# SK3000v1_-_3.net
KiCad netlist of a schematic drawn in EAGLE
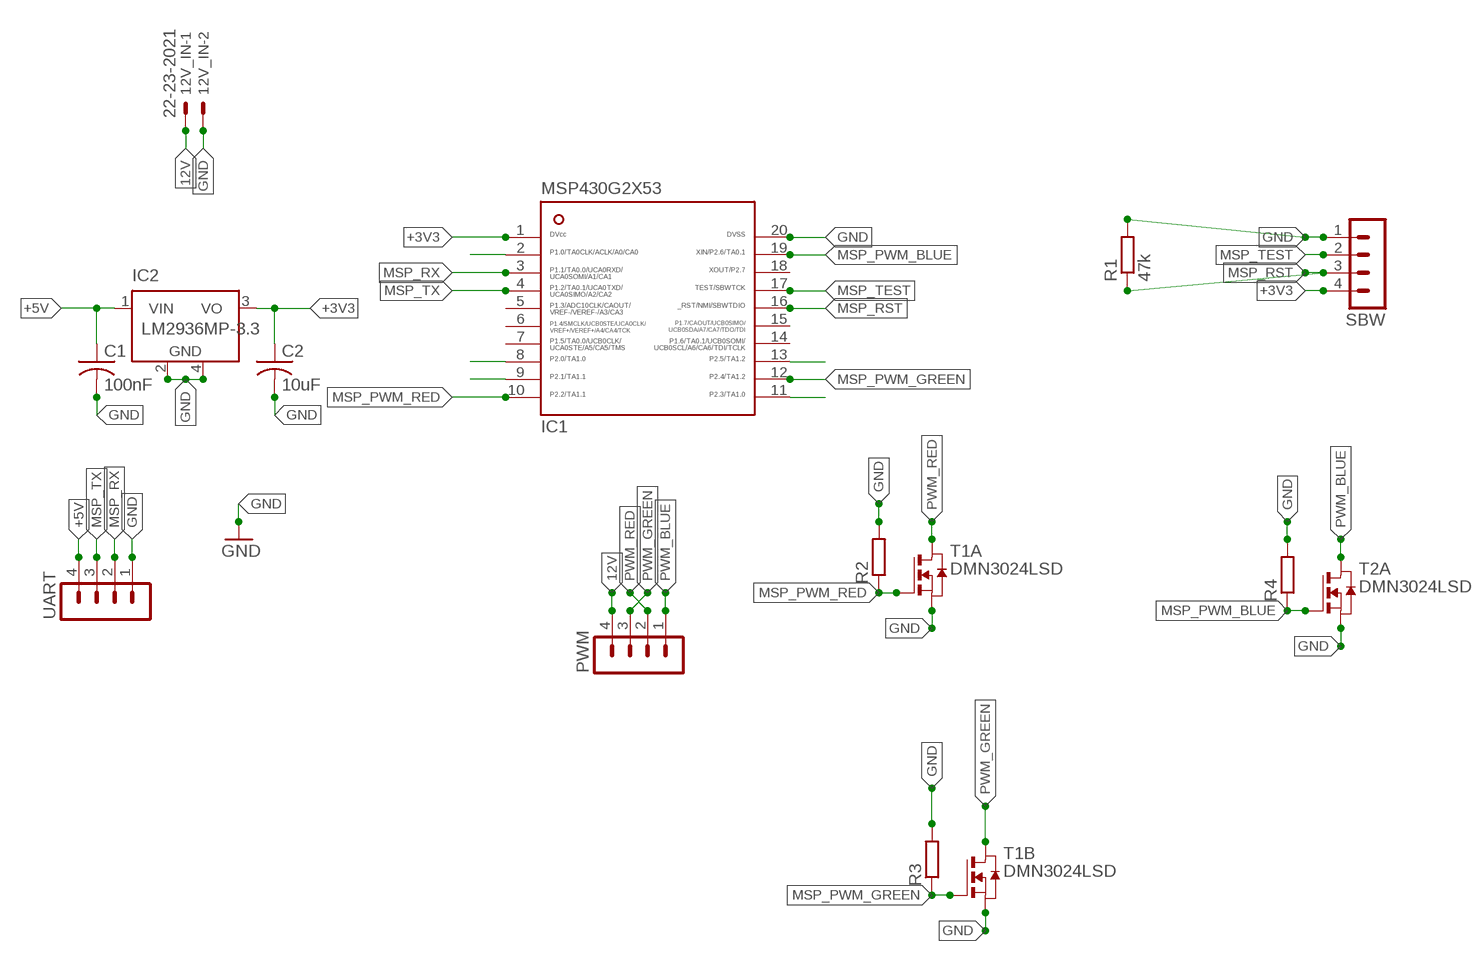
[diagram p0: schematic, sheet 1]

(export (version "E")
  (design (tool "Eeschema 10.0.6"))
  (components
    (comp (ref "12V_IN")
      (value "22-23-2021")
      (footprint "eagle-import:22-23-2021")
      (fields (field (name "MF") "MOLEX"))
      (libsource (lib "eagle-import") (part "22-23-2021"))
    )
    (comp (ref "C1")
      (value "100nF")
      (footprint "eagle-import:C025-024X044")
      (libsource (lib "eagle-import") (part "C-US025-024X044"))
    )
    (comp (ref "C2")
      (value "10uF")
      (footprint "eagle-import:C025-024X044")
      (libsource (lib "eagle-import") (part "C-US025-024X044"))
    )
    (comp (ref "IC1")
      (value "MSP430G2X53-20PW20")
      (footprint "eagle-import:PW20")
      (libsource (lib "eagle-import") (part "MSP430G2X53-20PW20"))
    )
    (comp (ref "IC2")
      (value "LM2936MP-3.3")
      (footprint "eagle-import:SOT223")
      (fields (field (name "MF") "NATIONAL SEMICONDUCTOR") (field (name "MPN") "LM2936MP-3.3/NOPB"))
      (libsource (lib "eagle-import") (part "LM2936MP?-3.3"))
    )
    (comp (ref "PWM")
      (value "MA04-1")
      (footprint "eagle-import:MA04-1")
      (libsource (lib "eagle-import") (part "MA04-1"))
    )
    (comp (ref "R1")
      (value "47k")
      (footprint "eagle-import:R0603")
      (libsource (lib "eagle-import") (part "R-EU_R0603"))
    )
    (comp (ref "R2")
      (value "R-EU_R0603")
      (footprint "eagle-import:R0603")
      (libsource (lib "eagle-import") (part "R-EU_R0603"))
    )
    (comp (ref "R3")
      (value "R-EU_R0603")
      (footprint "eagle-import:R0603")
      (libsource (lib "eagle-import") (part "R-EU_R0603"))
    )
    (comp (ref "R4")
      (value "R-EU_R0603")
      (footprint "eagle-import:R0603")
      (libsource (lib "eagle-import") (part "R-EU_R0603"))
    )
    (comp (ref "SBW")
      (value "MA04-1")
      (footprint "eagle-import:MA04-1")
      (libsource (lib "eagle-import") (part "MA04-1"))
    )
    (comp (ref "T1")
      (value "DMN3024LSD")
      (footprint "eagle-import:SO8")
      (libsource (lib "eagle-import") (part "DMN3024LSD"))
    )
    (comp (ref "T2")
      (value "DMN3024LSD")
      (footprint "eagle-import:SO8")
      (libsource (lib "eagle-import") (part "DMN3024LSD"))
    )
    (comp (ref "UART")
      (value "MA04-1")
      (footprint "eagle-import:MA04-1")
      (libsource (lib "eagle-import") (part "MA04-1"))
    )
  )
  (nets
    (net (code "1") (name "+3V3") (class "Default")
      (node (ref "C2") (pin "1") (pinfunction "1_1") (pintype "passive"))
      (node (ref "IC1") (pin "1") (pinfunction "1_1") (pintype "bidirectional"))
      (node (ref "IC2") (pin "3") (pinfunction "VO_3") (pintype "passive"))
      (node (ref "SBW") (pin "4") (pinfunction "4_4") (pintype "passive"))
    )
    (net (code "2") (name "+5V") (class "Default")
      (node (ref "C1") (pin "1") (pinfunction "1_1") (pintype "passive"))
      (node (ref "IC2") (pin "1") (pinfunction "VIN_1") (pintype "input"))
      (node (ref "UART") (pin "4") (pinfunction "4_4") (pintype "passive"))
    )
    (net (code "3") (name "12V") (class "Default")
      (node (ref "12V_IN") (pin "1") (pinfunction "S_1") (pintype "passive"))
      (node (ref "PWM") (pin "4") (pinfunction "4_4") (pintype "passive"))
    )
    (net (code "4") (name "GND") (class "Default")
      (node (ref "12V_IN") (pin "2") (pinfunction "S_2") (pintype "passive"))
      (node (ref "C1") (pin "2") (pinfunction "2_2") (pintype "passive"))
      (node (ref "C2") (pin "2") (pinfunction "2_2") (pintype "passive"))
      (node (ref "IC1") (pin "20") (pinfunction "20_20") (pintype "bidirectional"))
      (node (ref "IC2") (pin "2") (pinfunction "GND_2") (pintype "passive"))
      (node (ref "IC2") (pin "4") (pinfunction "GND_4") (pintype "passive"))
      (node (ref "R1") (pin "2") (pinfunction "2_2") (pintype "passive"))
      (node (ref "R2") (pin "2") (pinfunction "2_2") (pintype "passive"))
      (node (ref "R3") (pin "2") (pinfunction "2_2") (pintype "passive"))
      (node (ref "R4") (pin "2") (pinfunction "2_2") (pintype "passive"))
      (node (ref "SBW") (pin "1") (pinfunction "1_1") (pintype "passive"))
      (node (ref "T1") (pin "1") (pinfunction "S_1") (pintype "passive"))
      (node (ref "T1") (pin "3") (pinfunction "S_3") (pintype "passive"))
      (node (ref "T2") (pin "1") (pinfunction "S_1") (pintype "passive"))
      (node (ref "UART") (pin "1") (pinfunction "1_1") (pintype "passive"))
    )
    (net (code "5") (name "MSP_PWM_BLUE") (class "Default")
      (node (ref "IC1") (pin "19") (pinfunction "19_19") (pintype "bidirectional"))
      (node (ref "R4") (pin "1") (pinfunction "1_1") (pintype "passive"))
      (node (ref "T2") (pin "2") (pinfunction "G_2") (pintype "passive"))
    )
    (net (code "6") (name "MSP_PWM_GREEN") (class "Default")
      (node (ref "IC1") (pin "12") (pinfunction "12_12") (pintype "bidirectional"))
      (node (ref "R3") (pin "1") (pinfunction "1_1") (pintype "passive"))
      (node (ref "T1") (pin "4") (pinfunction "G_4") (pintype "passive"))
    )
    (net (code "7") (name "MSP_PWM_RED") (class "Default")
      (node (ref "IC1") (pin "10") (pinfunction "10_10") (pintype "bidirectional"))
      (node (ref "R2") (pin "1") (pinfunction "1_1") (pintype "passive"))
      (node (ref "T1") (pin "2") (pinfunction "G_2") (pintype "passive"))
    )
    (net (code "8") (name "MSP_RST") (class "Default")
      (node (ref "IC1") (pin "16") (pinfunction "16_16") (pintype "bidirectional"))
      (node (ref "R1") (pin "1") (pinfunction "1_1") (pintype "passive"))
      (node (ref "SBW") (pin "3") (pinfunction "3_3") (pintype "passive"))
    )
    (net (code "9") (name "MSP_RX") (class "Default")
      (node (ref "IC1") (pin "3") (pinfunction "3_3") (pintype "bidirectional"))
      (node (ref "UART") (pin "2") (pinfunction "2_2") (pintype "passive"))
    )
    (net (code "10") (name "MSP_TEST") (class "Default")
      (node (ref "IC1") (pin "17") (pinfunction "17_17") (pintype "bidirectional"))
      (node (ref "SBW") (pin "2") (pinfunction "2_2") (pintype "passive"))
    )
    (net (code "11") (name "MSP_TX") (class "Default")
      (node (ref "IC1") (pin "4") (pinfunction "4_4") (pintype "bidirectional"))
      (node (ref "UART") (pin "3") (pinfunction "3_3") (pintype "passive"))
    )
    (net (code "12") (name "PWM_BLUE") (class "Default")
      (node (ref "PWM") (pin "1") (pinfunction "1_1") (pintype "passive"))
      (node (ref "T2") (pin "7") (pinfunction "D_7") (pintype "passive"))
      (node (ref "T2") (pin "8") (pinfunction "D_8") (pintype "passive"))
    )
    (net (code "13") (name "PWM_GREEN") (class "Default")
      (node (ref "PWM") (pin "3") (pinfunction "3_3") (pintype "passive"))
      (node (ref "T1") (pin "5") (pinfunction "D_5") (pintype "passive"))
      (node (ref "T1") (pin "6") (pinfunction "D_6") (pintype "passive"))
    )
    (net (code "14") (name "PWM_RED") (class "Default")
      (node (ref "PWM") (pin "2") (pinfunction "2_2") (pintype "passive"))
      (node (ref "T1") (pin "7") (pinfunction "D_7") (pintype "passive"))
      (node (ref "T1") (pin "8") (pinfunction "D_8") (pintype "passive"))
    )
    (net (code "15") (name "unconnected-(IC1-Pad2)") (class "Default")
      (node (ref "IC1") (pin "2") (pinfunction "2_2") (pintype "bidirectional"))
    )
    (net (code "16") (name "unconnected-(IC1-Pad5)") (class "Default")
      (node (ref "IC1") (pin "5") (pinfunction "5_5") (pintype "bidirectional"))
    )
    (net (code "17") (name "unconnected-(IC1-Pad6)") (class "Default")
      (node (ref "IC1") (pin "6") (pinfunction "6_6") (pintype "bidirectional"))
    )
    (net (code "18") (name "unconnected-(IC1-Pad7)") (class "Default")
      (node (ref "IC1") (pin "7") (pinfunction "7_7") (pintype "bidirectional"))
    )
    (net (code "19") (name "unconnected-(IC1-Pad8)") (class "Default")
      (node (ref "IC1") (pin "8") (pinfunction "8_8") (pintype "bidirectional"))
    )
    (net (code "20") (name "unconnected-(IC1-Pad9)") (class "Default")
      (node (ref "IC1") (pin "9") (pinfunction "9_9") (pintype "bidirectional"))
    )
    (net (code "21") (name "unconnected-(IC1-Pad11)") (class "Default")
      (node (ref "IC1") (pin "11") (pinfunction "11_11") (pintype "bidirectional"))
    )
    (net (code "22") (name "unconnected-(IC1-Pad13)") (class "Default")
      (node (ref "IC1") (pin "13") (pinfunction "13_13") (pintype "bidirectional"))
    )
    (net (code "23") (name "unconnected-(IC1-Pad14)") (class "Default")
      (node (ref "IC1") (pin "14") (pinfunction "14_14") (pintype "bidirectional"))
    )
    (net (code "24") (name "unconnected-(IC1-Pad15)") (class "Default")
      (node (ref "IC1") (pin "15") (pinfunction "15_15") (pintype "bidirectional"))
    )
    (net (code "25") (name "unconnected-(IC1-Pad18)") (class "Default")
      (node (ref "IC1") (pin "18") (pinfunction "18_18") (pintype "bidirectional"))
    )
  )
)
